# ExpansionBoard.net
KiCad netlist of a schematic drawn in Altium Designer
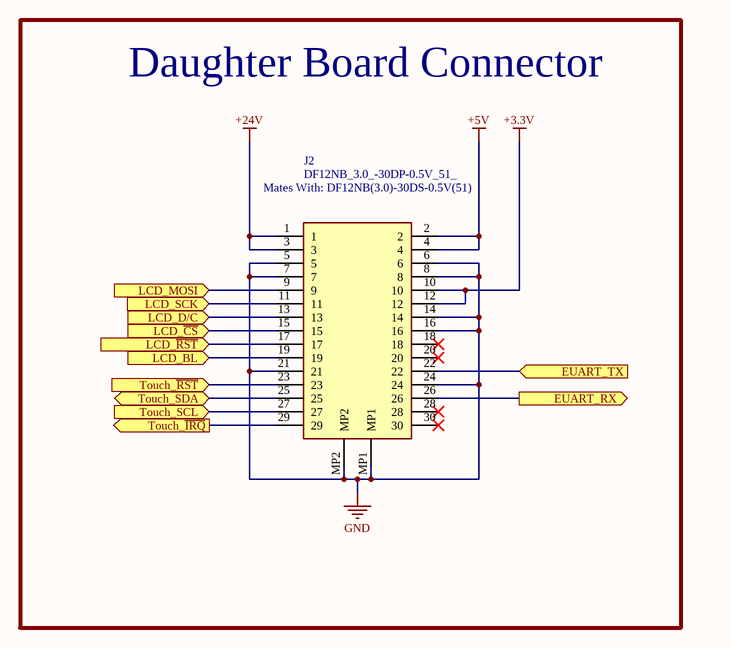
[diagram p0: ExpansionBoard.SchDoc]

(export (version "E")
  (design (tool "Eeschema 10.0.6"))
  (components
    (comp (ref "J2")
      (value "DF12NB_3.0_-30DP-0.5V_51_")
      (footprint "SamacSys:DF12NB3030DP05V51")
      (description "Connector")
      (fields
        (field (name "MANUFACTURER_PART_NUMBER") "DF12NB(3.0)-30DP-0.5V(51)")
        (field (name "MOUSER PART NUMBER") "798-DF12NB3030DP0551")
      )
      (libsource (lib "SomoPowerPackControl") (part "DF12NB_3.0_-30DP-0.5V_51_"))
    )
  )
  (nets
    (net (code "1") (name "+3.3V") (class "Default")
      (node (ref "J2") (pin "10") (pinfunction "10_10") (pintype "passive"))
      (node (ref "J2") (pin "12") (pinfunction "12_12") (pintype "passive"))
    )
    (net (code "2") (name "+5V") (class "Default")
      (node (ref "J2") (pin "2") (pinfunction "2_2") (pintype "passive"))
      (node (ref "J2") (pin "4") (pinfunction "4_4") (pintype "passive"))
    )
    (net (code "3") (name "+24V") (class "Default")
      (node (ref "J2") (pin "1") (pinfunction "1_1") (pintype "passive"))
      (node (ref "J2") (pin "3") (pinfunction "3_3") (pintype "passive"))
    )
    (net (code "4") (name "/EUART_RX") (class "Default")
      (node (ref "J2") (pin "26") (pinfunction "26_26") (pintype "passive"))
    )
    (net (code "5") (name "/EUART_TX") (class "Default")
      (node (ref "J2") (pin "22") (pinfunction "22_22") (pintype "passive"))
    )
    (net (code "6") (name "/LCD_BL") (class "Default")
      (node (ref "J2") (pin "19") (pinfunction "19_19") (pintype "passive"))
    )
    (net (code "7") (name "/LCD_D{slash}C") (class "Default")
      (node (ref "J2") (pin "13") (pinfunction "13_13") (pintype "passive"))
    )
    (net (code "8") (name "/LCD_MOSI") (class "Default")
      (node (ref "J2") (pin "9") (pinfunction "9_9") (pintype "passive"))
    )
    (net (code "9") (name "/LCD_SCK") (class "Default")
      (node (ref "J2") (pin "11") (pinfunction "11_11") (pintype "passive"))
    )
    (net (code "10") (name "/LCD_~{CS}") (class "Default")
      (node (ref "J2") (pin "15") (pinfunction "15_15") (pintype "passive"))
    )
    (net (code "11") (name "/LCD_~{RST}") (class "Default")
      (node (ref "J2") (pin "17") (pinfunction "17_17") (pintype "passive"))
    )
    (net (code "12") (name "/Touch_SCL") (class "Default")
      (node (ref "J2") (pin "27") (pinfunction "27_27") (pintype "passive"))
    )
    (net (code "13") (name "/Touch_SDA") (class "Default")
      (node (ref "J2") (pin "25") (pinfunction "25_25") (pintype "passive"))
    )
    (net (code "14") (name "/Touch_~{IRQ}") (class "Default")
      (node (ref "J2") (pin "29") (pinfunction "29_29") (pintype "passive"))
    )
    (net (code "15") (name "/Touch_~{RST}") (class "Default")
      (node (ref "J2") (pin "23") (pinfunction "23_23") (pintype "passive"))
    )
    (net (code "16") (name "GND") (class "Default")
      (node (ref "J2") (pin "14") (pinfunction "14_14") (pintype "passive"))
      (node (ref "J2") (pin "16") (pinfunction "16_16") (pintype "passive"))
      (node (ref "J2") (pin "21") (pinfunction "21_21") (pintype "passive"))
      (node (ref "J2") (pin "24") (pinfunction "24_24") (pintype "passive"))
      (node (ref "J2") (pin "5") (pinfunction "5_5") (pintype "passive"))
      (node (ref "J2") (pin "6") (pinfunction "6_6") (pintype "passive"))
      (node (ref "J2") (pin "7") (pinfunction "7_7") (pintype "passive"))
      (node (ref "J2") (pin "8") (pinfunction "8_8") (pintype "passive"))
      (node (ref "J2") (pin "MP1") (pinfunction "MP1_MP1") (pintype "passive"))
      (node (ref "J2") (pin "MP2") (pinfunction "MP2_MP2") (pintype "passive"))
    )
    (net (code "17") (name "unconnected-(J2-Pad18)") (class "Default")
      (node (ref "J2") (pin "18") (pinfunction "18_18") (pintype "passive+no_connect"))
    )
    (net (code "18") (name "unconnected-(J2-Pad20)") (class "Default")
      (node (ref "J2") (pin "20") (pinfunction "20_20") (pintype "passive+no_connect"))
    )
    (net (code "19") (name "unconnected-(J2-Pad28)") (class "Default")
      (node (ref "J2") (pin "28") (pinfunction "28_28") (pintype "passive+no_connect"))
    )
    (net (code "20") (name "unconnected-(J2-Pad30)") (class "Default")
      (node (ref "J2") (pin "30") (pinfunction "30_30") (pintype "passive+no_connect"))
    )
  )
)
